# Motor_PCB.net
KiCad netlist of a schematic drawn in EAGLE
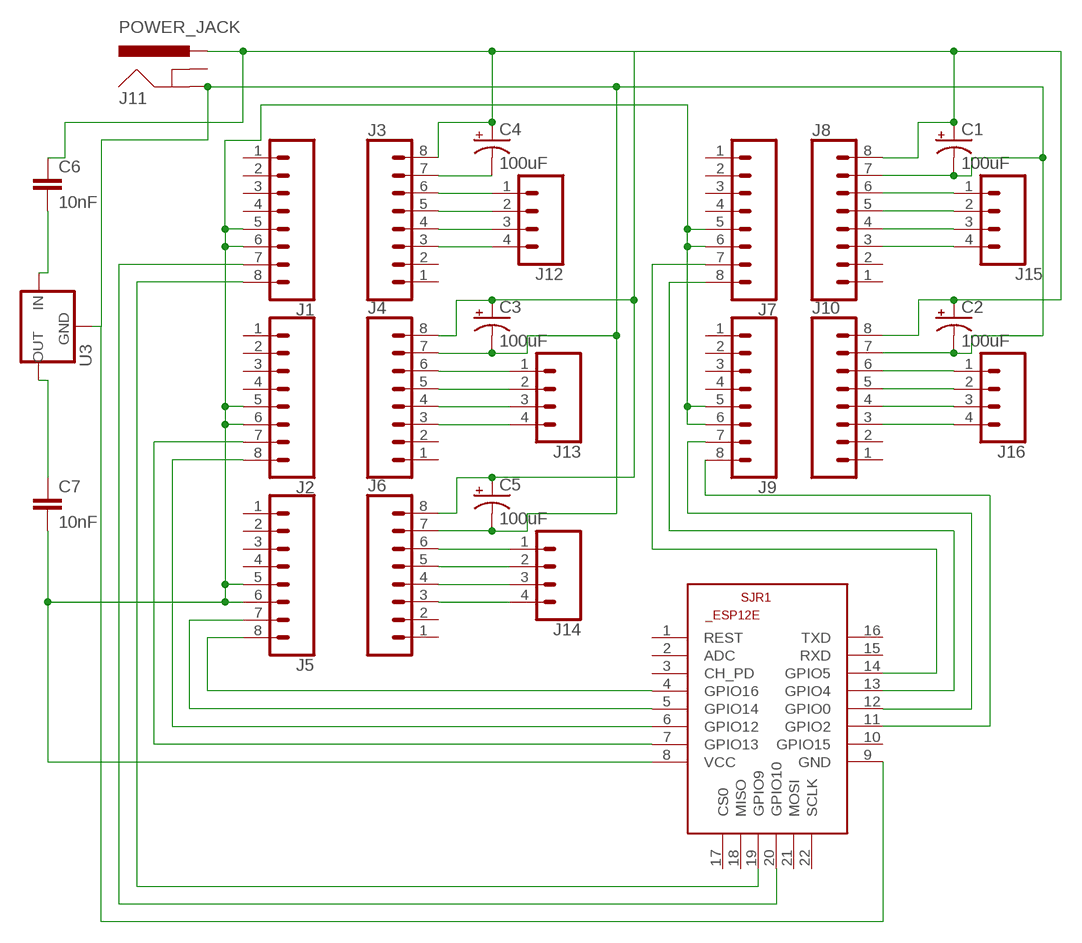
[diagram p0: schematic, sheet 1]

(export (version "E")
  (design (tool "Eeschema 10.0.6"))
  (components
    (comp (ref "C1")
      (value "100uF")
      (footprint "eagle-import:EIA7343")
      (libsource (lib "eagle-import") (part "100UF-POLAR-EIA7343-16V-10%(TANT)"))
    )
    (comp (ref "C2")
      (value "100uF")
      (footprint "eagle-import:EIA7343")
      (libsource (lib "eagle-import") (part "100UF-POLAR-EIA7343-16V-10%(TANT)"))
    )
    (comp (ref "C3")
      (value "100uF")
      (footprint "eagle-import:EIA7343")
      (libsource (lib "eagle-import") (part "100UF-POLAR-EIA7343-16V-10%(TANT)"))
    )
    (comp (ref "C4")
      (value "100uF")
      (footprint "eagle-import:EIA7343")
      (libsource (lib "eagle-import") (part "100UF-POLAR-EIA7343-16V-10%(TANT)"))
    )
    (comp (ref "C5")
      (value "100uF")
      (footprint "eagle-import:EIA7343")
      (libsource (lib "eagle-import") (part "100UF-POLAR-EIA7343-16V-10%(TANT)"))
    )
    (comp (ref "C6")
      (value "10nF")
      (footprint "eagle-import:0603")
      (libsource (lib "eagle-import") (part "10NF-0603-50V-10%"))
    )
    (comp (ref "C7")
      (value "10nF")
      (footprint "eagle-import:0603")
      (libsource (lib "eagle-import") (part "10NF-0603-50V-10%"))
    )
    (comp (ref "J1")
      (value "CONN_08\"")
      (footprint "eagle-import:1X08")
      (libsource (lib "eagle-import") (part "CONN_08{dblquote}"))
    )
    (comp (ref "J2")
      (value "CONN_08\"")
      (footprint "eagle-import:1X08")
      (libsource (lib "eagle-import") (part "CONN_08{dblquote}"))
    )
    (comp (ref "J3")
      (value "CONN_08\"")
      (footprint "eagle-import:1X08")
      (libsource (lib "eagle-import") (part "CONN_08{dblquote}"))
    )
    (comp (ref "J4")
      (value "CONN_08\"")
      (footprint "eagle-import:1X08")
      (libsource (lib "eagle-import") (part "CONN_08{dblquote}"))
    )
    (comp (ref "J5")
      (value "CONN_08\"")
      (footprint "eagle-import:1X08")
      (libsource (lib "eagle-import") (part "CONN_08{dblquote}"))
    )
    (comp (ref "J6")
      (value "CONN_08\"")
      (footprint "eagle-import:1X08")
      (libsource (lib "eagle-import") (part "CONN_08{dblquote}"))
    )
    (comp (ref "J7")
      (value "CONN_08\"")
      (footprint "eagle-import:1X08")
      (libsource (lib "eagle-import") (part "CONN_08{dblquote}"))
    )
    (comp (ref "J8")
      (value "CONN_08\"")
      (footprint "eagle-import:1X08")
      (libsource (lib "eagle-import") (part "CONN_08{dblquote}"))
    )
    (comp (ref "J9")
      (value "CONN_08\"")
      (footprint "eagle-import:1X08")
      (libsource (lib "eagle-import") (part "CONN_08{dblquote}"))
    )
    (comp (ref "J10")
      (value "CONN_08\"")
      (footprint "eagle-import:1X08")
      (libsource (lib "eagle-import") (part "CONN_08{dblquote}"))
    )
    (comp (ref "J11")
      (value "POWER_JACK")
      (footprint "eagle-import:POWER_JACK_PTH")
      (libsource (lib "eagle-import") (part "POWER_JACK"))
    )
    (comp (ref "J12")
      (value "CONN_04JST-PTH-VERT")
      (footprint "eagle-import:JST-4-PTH-VERT")
      (libsource (lib "eagle-import") (part "CONN_04JST-PTH-VERT"))
    )
    (comp (ref "J13")
      (value "CONN_04JST-PTH-VERT")
      (footprint "eagle-import:JST-4-PTH-VERT")
      (libsource (lib "eagle-import") (part "CONN_04JST-PTH-VERT"))
    )
    (comp (ref "J14")
      (value "CONN_04JST-PTH-VERT")
      (footprint "eagle-import:JST-4-PTH-VERT")
      (libsource (lib "eagle-import") (part "CONN_04JST-PTH-VERT"))
    )
    (comp (ref "J15")
      (value "CONN_04JST-PTH-VERT")
      (footprint "eagle-import:JST-4-PTH-VERT")
      (libsource (lib "eagle-import") (part "CONN_04JST-PTH-VERT"))
    )
    (comp (ref "J16")
      (value "CONN_04JST-PTH-VERT")
      (footprint "eagle-import:JST-4-PTH-VERT")
      (libsource (lib "eagle-import") (part "CONN_04JST-PTH-VERT"))
    )
    (comp (ref "SJR1")
      (value "ESP8266-12EESP12E")
      (footprint "eagle-import:ESP8266-ESP12E")
      (libsource (lib "eagle-import") (part "ESP8266-12EESP12E"))
    )
    (comp (ref "U3")
      (value "V_REG_78XX-TO-220")
      (footprint "eagle-import:TO-220-ALT")
      (libsource (lib "eagle-import") (part "V_REG_78XX-TO-220"))
    )
  )
  (nets
    (net (code "1") (name "Net-(C1-+)") (class "Default")
      (node (ref "C1") (pin "A") (pinfunction "+_A") (pintype "passive"))
      (node (ref "C2") (pin "A") (pinfunction "+_A") (pintype "passive"))
      (node (ref "C3") (pin "A") (pinfunction "+_A") (pintype "passive"))
      (node (ref "C4") (pin "A") (pinfunction "+_A") (pintype "passive"))
      (node (ref "C5") (pin "A") (pinfunction "+_A") (pintype "passive"))
      (node (ref "C6") (pin "1") (pinfunction "1_1") (pintype "passive"))
      (node (ref "J10") (pin "8") (pinfunction "8_8") (pintype "passive"))
      (node (ref "J11") (pin "PWR") (pinfunction "PWR_PWR") (pintype "bidirectional"))
      (node (ref "J3") (pin "8") (pinfunction "8_8") (pintype "passive"))
      (node (ref "J4") (pin "8") (pinfunction "8_8") (pintype "passive"))
      (node (ref "J6") (pin "8") (pinfunction "8_8") (pintype "passive"))
      (node (ref "J8") (pin "8") (pinfunction "8_8") (pintype "passive"))
    )
    (net (code "2") (name "Net-(C1--)") (class "Default")
      (node (ref "C1") (pin "C") (pinfunction "-_C") (pintype "passive"))
      (node (ref "C2") (pin "C") (pinfunction "-_C") (pintype "passive"))
      (node (ref "C3") (pin "C") (pinfunction "-_C") (pintype "passive"))
      (node (ref "C5") (pin "C") (pinfunction "-_C") (pintype "passive"))
      (node (ref "J10") (pin "7") (pinfunction "7_7") (pintype "passive"))
      (node (ref "J11") (pin "GND") (pinfunction "GND_GND") (pintype "bidirectional"))
      (node (ref "J4") (pin "7") (pinfunction "7_7") (pintype "passive"))
      (node (ref "J6") (pin "7") (pinfunction "7_7") (pintype "passive"))
      (node (ref "J8") (pin "7") (pinfunction "7_7") (pintype "passive"))
      (node (ref "SJR1") (pin "9") (pinfunction "GND_9") (pintype "bidirectional"))
      (node (ref "U3") (pin "GND") (pinfunction "GND_GND") (pintype "input"))
    )
    (net (code "3") (name "Net-(C4--)") (class "Default")
      (node (ref "C4") (pin "C") (pinfunction "-_C") (pintype "passive"))
      (node (ref "J3") (pin "7") (pinfunction "7_7") (pintype "passive"))
    )
    (net (code "4") (name "Net-(C6-Pad2)") (class "Default")
      (node (ref "C6") (pin "2") (pinfunction "2_2") (pintype "passive"))
      (node (ref "U3") (pin "IN") (pinfunction "IN_IN") (pintype "input"))
    )
    (net (code "5") (name "Net-(C7-Pad1)") (class "Default")
      (node (ref "C7") (pin "1") (pinfunction "1_1") (pintype "passive"))
      (node (ref "U3") (pin "OUT") (pinfunction "OUT_OUT") (pintype "passive"))
    )
    (net (code "6") (name "Net-(J10-Pad3)") (class "Default")
      (node (ref "J10") (pin "3") (pinfunction "3_3") (pintype "passive"))
      (node (ref "J16") (pin "4") (pinfunction "4_4") (pintype "passive"))
    )
    (net (code "7") (name "Net-(J10-Pad4)") (class "Default")
      (node (ref "J10") (pin "4") (pinfunction "4_4") (pintype "passive"))
      (node (ref "J16") (pin "3") (pinfunction "3_3") (pintype "passive"))
    )
    (net (code "8") (name "Net-(J10-Pad5)") (class "Default")
      (node (ref "J10") (pin "5") (pinfunction "5_5") (pintype "passive"))
      (node (ref "J16") (pin "2") (pinfunction "2_2") (pintype "passive"))
    )
    (net (code "9") (name "Net-(J10-Pad6)") (class "Default")
      (node (ref "J10") (pin "6") (pinfunction "6_6") (pintype "passive"))
      (node (ref "J16") (pin "1") (pinfunction "1_1") (pintype "passive"))
    )
    (net (code "10") (name "Net-(J12-Pad1)") (class "Default")
      (node (ref "J12") (pin "1") (pinfunction "1_1") (pintype "passive"))
      (node (ref "J3") (pin "6") (pinfunction "6_6") (pintype "passive"))
    )
    (net (code "11") (name "Net-(J12-Pad2)") (class "Default")
      (node (ref "J12") (pin "2") (pinfunction "2_2") (pintype "passive"))
      (node (ref "J3") (pin "5") (pinfunction "5_5") (pintype "passive"))
    )
    (net (code "12") (name "Net-(J12-Pad3)") (class "Default")
      (node (ref "J12") (pin "3") (pinfunction "3_3") (pintype "passive"))
      (node (ref "J3") (pin "4") (pinfunction "4_4") (pintype "passive"))
    )
    (net (code "13") (name "Net-(J12-Pad4)") (class "Default")
      (node (ref "J12") (pin "4") (pinfunction "4_4") (pintype "passive"))
      (node (ref "J3") (pin "3") (pinfunction "3_3") (pintype "passive"))
    )
    (net (code "14") (name "Net-(J13-Pad1)") (class "Default")
      (node (ref "J13") (pin "1") (pinfunction "1_1") (pintype "passive"))
      (node (ref "J4") (pin "6") (pinfunction "6_6") (pintype "passive"))
    )
    (net (code "15") (name "Net-(J13-Pad2)") (class "Default")
      (node (ref "J13") (pin "2") (pinfunction "2_2") (pintype "passive"))
      (node (ref "J4") (pin "5") (pinfunction "5_5") (pintype "passive"))
    )
    (net (code "16") (name "Net-(J13-Pad3)") (class "Default")
      (node (ref "J13") (pin "3") (pinfunction "3_3") (pintype "passive"))
      (node (ref "J4") (pin "4") (pinfunction "4_4") (pintype "passive"))
    )
    (net (code "17") (name "Net-(J13-Pad4)") (class "Default")
      (node (ref "J13") (pin "4") (pinfunction "4_4") (pintype "passive"))
      (node (ref "J4") (pin "3") (pinfunction "3_3") (pintype "passive"))
    )
    (net (code "18") (name "Net-(J14-Pad1)") (class "Default")
      (node (ref "J14") (pin "1") (pinfunction "1_1") (pintype "passive"))
      (node (ref "J6") (pin "6") (pinfunction "6_6") (pintype "passive"))
    )
    (net (code "19") (name "Net-(J14-Pad2)") (class "Default")
      (node (ref "J14") (pin "2") (pinfunction "2_2") (pintype "passive"))
      (node (ref "J6") (pin "5") (pinfunction "5_5") (pintype "passive"))
    )
    (net (code "20") (name "Net-(J14-Pad3)") (class "Default")
      (node (ref "J14") (pin "3") (pinfunction "3_3") (pintype "passive"))
      (node (ref "J6") (pin "4") (pinfunction "4_4") (pintype "passive"))
    )
    (net (code "21") (name "Net-(J14-Pad4)") (class "Default")
      (node (ref "J14") (pin "4") (pinfunction "4_4") (pintype "passive"))
      (node (ref "J6") (pin "3") (pinfunction "3_3") (pintype "passive"))
    )
    (net (code "22") (name "Net-(J15-Pad1)") (class "Default")
      (node (ref "J15") (pin "1") (pinfunction "1_1") (pintype "passive"))
      (node (ref "J8") (pin "6") (pinfunction "6_6") (pintype "passive"))
    )
    (net (code "23") (name "Net-(J15-Pad2)") (class "Default")
      (node (ref "J15") (pin "2") (pinfunction "2_2") (pintype "passive"))
      (node (ref "J8") (pin "5") (pinfunction "5_5") (pintype "passive"))
    )
    (net (code "24") (name "Net-(J15-Pad3)") (class "Default")
      (node (ref "J15") (pin "3") (pinfunction "3_3") (pintype "passive"))
      (node (ref "J8") (pin "4") (pinfunction "4_4") (pintype "passive"))
    )
    (net (code "25") (name "Net-(J15-Pad4)") (class "Default")
      (node (ref "J15") (pin "4") (pinfunction "4_4") (pintype "passive"))
      (node (ref "J8") (pin "3") (pinfunction "3_3") (pintype "passive"))
    )
    (net (code "26") (name "Net-(SJR1-GPIO0)") (class "Default")
      (node (ref "J9") (pin "7") (pinfunction "7_7") (pintype "passive"))
      (node (ref "SJR1") (pin "12") (pinfunction "GPIO0_12") (pintype "bidirectional"))
    )
    (net (code "27") (name "Net-(SJR1-GPIO2)") (class "Default")
      (node (ref "J9") (pin "8") (pinfunction "8_8") (pintype "passive"))
      (node (ref "SJR1") (pin "11") (pinfunction "GPIO2_11") (pintype "bidirectional"))
    )
    (net (code "28") (name "Net-(SJR1-GPIO4)") (class "Default")
      (node (ref "J7") (pin "8") (pinfunction "8_8") (pintype "passive"))
      (node (ref "SJR1") (pin "13") (pinfunction "GPIO4_13") (pintype "bidirectional"))
    )
    (net (code "29") (name "Net-(SJR1-GPIO5)") (class "Default")
      (node (ref "J7") (pin "7") (pinfunction "7_7") (pintype "passive"))
      (node (ref "SJR1") (pin "14") (pinfunction "GPIO5_14") (pintype "bidirectional"))
    )
    (net (code "30") (name "Net-(SJR1-GPIO9)") (class "Default")
      (node (ref "J1") (pin "8") (pinfunction "8_8") (pintype "passive"))
      (node (ref "SJR1") (pin "19") (pinfunction "GPIO9_19") (pintype "bidirectional"))
    )
    (net (code "31") (name "Net-(SJR1-GPIO10)") (class "Default")
      (node (ref "J1") (pin "7") (pinfunction "7_7") (pintype "passive"))
      (node (ref "SJR1") (pin "20") (pinfunction "GPIO10_20") (pintype "bidirectional"))
    )
    (net (code "32") (name "Net-(SJR1-GPIO12)") (class "Default")
      (node (ref "J2") (pin "8") (pinfunction "8_8") (pintype "passive"))
      (node (ref "SJR1") (pin "6") (pinfunction "GPIO12_6") (pintype "bidirectional"))
    )
    (net (code "33") (name "Net-(SJR1-GPIO13)") (class "Default")
      (node (ref "J2") (pin "7") (pinfunction "7_7") (pintype "passive"))
      (node (ref "SJR1") (pin "7") (pinfunction "GPIO13_7") (pintype "bidirectional"))
    )
    (net (code "34") (name "Net-(SJR1-GPIO14)") (class "Default")
      (node (ref "J5") (pin "7") (pinfunction "7_7") (pintype "passive"))
      (node (ref "SJR1") (pin "5") (pinfunction "GPIO14_5") (pintype "bidirectional"))
    )
    (net (code "35") (name "Net-(SJR1-GPIO16)") (class "Default")
      (node (ref "J5") (pin "8") (pinfunction "8_8") (pintype "passive"))
      (node (ref "SJR1") (pin "4") (pinfunction "GPIO16_4") (pintype "bidirectional"))
    )
    (net (code "36") (name "Net-(SJR1-VCC)") (class "Default")
      (node (ref "C7") (pin "2") (pinfunction "2_2") (pintype "passive"))
      (node (ref "J1") (pin "5") (pinfunction "5_5") (pintype "passive"))
      (node (ref "J1") (pin "6") (pinfunction "6_6") (pintype "passive"))
      (node (ref "J2") (pin "5") (pinfunction "5_5") (pintype "passive"))
      (node (ref "J2") (pin "6") (pinfunction "6_6") (pintype "passive"))
      (node (ref "J5") (pin "5") (pinfunction "5_5") (pintype "passive"))
      (node (ref "J5") (pin "6") (pinfunction "6_6") (pintype "passive"))
      (node (ref "J7") (pin "5") (pinfunction "5_5") (pintype "passive"))
      (node (ref "J7") (pin "6") (pinfunction "6_6") (pintype "passive"))
      (node (ref "J9") (pin "5") (pinfunction "5_5") (pintype "passive"))
      (node (ref "J9") (pin "6") (pinfunction "6_6") (pintype "passive"))
      (node (ref "SJR1") (pin "8") (pinfunction "VCC_8") (pintype "bidirectional"))
    )
    (net (code "37") (name "unconnected-(J1-Pad1)") (class "Default")
      (node (ref "J1") (pin "1") (pinfunction "1_1") (pintype "passive"))
    )
    (net (code "38") (name "unconnected-(J1-Pad2)") (class "Default")
      (node (ref "J1") (pin "2") (pinfunction "2_2") (pintype "passive"))
    )
    (net (code "39") (name "unconnected-(J1-Pad3)") (class "Default")
      (node (ref "J1") (pin "3") (pinfunction "3_3") (pintype "passive"))
    )
    (net (code "40") (name "unconnected-(J1-Pad4)") (class "Default")
      (node (ref "J1") (pin "4") (pinfunction "4_4") (pintype "passive"))
    )
    (net (code "41") (name "unconnected-(J2-Pad1)") (class "Default")
      (node (ref "J2") (pin "1") (pinfunction "1_1") (pintype "passive"))
    )
    (net (code "42") (name "unconnected-(J2-Pad2)") (class "Default")
      (node (ref "J2") (pin "2") (pinfunction "2_2") (pintype "passive"))
    )
    (net (code "43") (name "unconnected-(J2-Pad3)") (class "Default")
      (node (ref "J2") (pin "3") (pinfunction "3_3") (pintype "passive"))
    )
    (net (code "44") (name "unconnected-(J2-Pad4)") (class "Default")
      (node (ref "J2") (pin "4") (pinfunction "4_4") (pintype "passive"))
    )
    (net (code "45") (name "unconnected-(J3-Pad1)") (class "Default")
      (node (ref "J3") (pin "1") (pinfunction "1_1") (pintype "passive"))
    )
    (net (code "46") (name "unconnected-(J3-Pad2)") (class "Default")
      (node (ref "J3") (pin "2") (pinfunction "2_2") (pintype "passive"))
    )
    (net (code "47") (name "unconnected-(J4-Pad1)") (class "Default")
      (node (ref "J4") (pin "1") (pinfunction "1_1") (pintype "passive"))
    )
    (net (code "48") (name "unconnected-(J4-Pad2)") (class "Default")
      (node (ref "J4") (pin "2") (pinfunction "2_2") (pintype "passive"))
    )
    (net (code "49") (name "unconnected-(J5-Pad1)") (class "Default")
      (node (ref "J5") (pin "1") (pinfunction "1_1") (pintype "passive"))
    )
    (net (code "50") (name "unconnected-(J5-Pad2)") (class "Default")
      (node (ref "J5") (pin "2") (pinfunction "2_2") (pintype "passive"))
    )
    (net (code "51") (name "unconnected-(J5-Pad3)") (class "Default")
      (node (ref "J5") (pin "3") (pinfunction "3_3") (pintype "passive"))
    )
    (net (code "52") (name "unconnected-(J5-Pad4)") (class "Default")
      (node (ref "J5") (pin "4") (pinfunction "4_4") (pintype "passive"))
    )
    (net (code "53") (name "unconnected-(J6-Pad1)") (class "Default")
      (node (ref "J6") (pin "1") (pinfunction "1_1") (pintype "passive"))
    )
    (net (code "54") (name "unconnected-(J6-Pad2)") (class "Default")
      (node (ref "J6") (pin "2") (pinfunction "2_2") (pintype "passive"))
    )
    (net (code "55") (name "unconnected-(J7-Pad1)") (class "Default")
      (node (ref "J7") (pin "1") (pinfunction "1_1") (pintype "passive"))
    )
    (net (code "56") (name "unconnected-(J7-Pad2)") (class "Default")
      (node (ref "J7") (pin "2") (pinfunction "2_2") (pintype "passive"))
    )
    (net (code "57") (name "unconnected-(J7-Pad3)") (class "Default")
      (node (ref "J7") (pin "3") (pinfunction "3_3") (pintype "passive"))
    )
    (net (code "58") (name "unconnected-(J7-Pad4)") (class "Default")
      (node (ref "J7") (pin "4") (pinfunction "4_4") (pintype "passive"))
    )
    (net (code "59") (name "unconnected-(J8-Pad1)") (class "Default")
      (node (ref "J8") (pin "1") (pinfunction "1_1") (pintype "passive"))
    )
    (net (code "60") (name "unconnected-(J8-Pad2)") (class "Default")
      (node (ref "J8") (pin "2") (pinfunction "2_2") (pintype "passive"))
    )
    (net (code "61") (name "unconnected-(J9-Pad1)") (class "Default")
      (node (ref "J9") (pin "1") (pinfunction "1_1") (pintype "passive"))
    )
    (net (code "62") (name "unconnected-(J9-Pad2)") (class "Default")
      (node (ref "J9") (pin "2") (pinfunction "2_2") (pintype "passive"))
    )
    (net (code "63") (name "unconnected-(J9-Pad3)") (class "Default")
      (node (ref "J9") (pin "3") (pinfunction "3_3") (pintype "passive"))
    )
    (net (code "64") (name "unconnected-(J9-Pad4)") (class "Default")
      (node (ref "J9") (pin "4") (pinfunction "4_4") (pintype "passive"))
    )
    (net (code "65") (name "unconnected-(J10-Pad1)") (class "Default")
      (node (ref "J10") (pin "1") (pinfunction "1_1") (pintype "passive"))
    )
    (net (code "66") (name "unconnected-(J10-Pad2)") (class "Default")
      (node (ref "J10") (pin "2") (pinfunction "2_2") (pintype "passive"))
    )
    (net (code "67") (name "unconnected-(J11-PadGNDBREAK)") (class "Default")
      (node (ref "J11") (pin "GNDBREAK") (pinfunction "GNDBREAK_GNDBREAK") (pintype "bidirectional"))
    )
    (net (code "68") (name "unconnected-(SJR1-ADC-Pad2)") (class "Default")
      (node (ref "SJR1") (pin "2") (pinfunction "ADC_2") (pintype "bidirectional"))
    )
    (net (code "69") (name "unconnected-(SJR1-CH_PD-Pad3)") (class "Default")
      (node (ref "SJR1") (pin "3") (pinfunction "CH_PD_3") (pintype "bidirectional"))
    )
    (net (code "70") (name "unconnected-(SJR1-CS0-Pad17)") (class "Default")
      (node (ref "SJR1") (pin "17") (pinfunction "CS0_17") (pintype "bidirectional"))
    )
    (net (code "71") (name "unconnected-(SJR1-GPIO15-Pad10)") (class "Default")
      (node (ref "SJR1") (pin "10") (pinfunction "GPIO15_10") (pintype "bidirectional"))
    )
    (net (code "72") (name "unconnected-(SJR1-MISO-Pad18)") (class "Default")
      (node (ref "SJR1") (pin "18") (pinfunction "MISO_18") (pintype "bidirectional"))
    )
    (net (code "73") (name "unconnected-(SJR1-MOSI-Pad21)") (class "Default")
      (node (ref "SJR1") (pin "21") (pinfunction "MOSI_21") (pintype "bidirectional"))
    )
    (net (code "74") (name "unconnected-(SJR1-REST-Pad1)") (class "Default")
      (node (ref "SJR1") (pin "1") (pinfunction "REST_1") (pintype "bidirectional"))
    )
    (net (code "75") (name "unconnected-(SJR1-RXD-Pad15)") (class "Default")
      (node (ref "SJR1") (pin "15") (pinfunction "RXD_15") (pintype "bidirectional"))
    )
    (net (code "76") (name "unconnected-(SJR1-SCLK-Pad22)") (class "Default")
      (node (ref "SJR1") (pin "22") (pinfunction "SCLK_22") (pintype "bidirectional"))
    )
    (net (code "77") (name "unconnected-(SJR1-TXD-Pad16)") (class "Default")
      (node (ref "SJR1") (pin "16") (pinfunction "TXD_16") (pintype "bidirectional"))
    )
  )
)
